# LickDetector.net
KiCad netlist of a schematic drawn in EAGLE
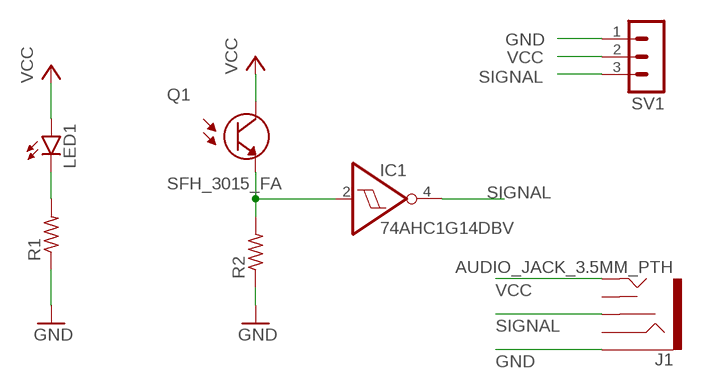
[diagram p0: schematic, sheet 1]

(export (version "E")
  (design (tool "Eeschema 10.0.6"))
  (components
    (comp (ref "IC1")
      (value "74AHC1G14DBV")
      (footprint "eagle-import:SOT23-5")
      (libsource (lib "eagle-import") (part "741G14DBVAHC"))
    )
    (comp (ref "J1")
      (value "AUDIO_JACK_3.5MM_PTH")
      (footprint "eagle-import:AUDIO-JACK")
      (libsource (lib "eagle-import") (part "AUDIO_JACK_3.5MM_PTH"))
    )
    (comp (ref "LED1")
      (value "LEDCHIPLED_1206")
      (footprint "eagle-import:CHIPLED_1206")
      (libsource (lib "eagle-import") (part "LEDCHIPLED_1206"))
    )
    (comp (ref "Q1")
      (value "SFH_3015_FA")
      (footprint "eagle-import:XDCR_SFH_3015_FA")
      (fields
        (field (name "DIGI-KEY_PART_NUMBER") "475-2914-1-ND")
        (field (name "MF") "OSRAM Opto")
        (field (name "MP") "SFH 3015 FA")
      )
      (libsource (lib "eagle-import") (part "SFH_3015_FA"))
    )
    (comp (ref "R1")
      (value "R-US_M1206")
      (footprint "eagle-import:M1206")
      (libsource (lib "eagle-import") (part "R-US_M1206"))
    )
    (comp (ref "R2")
      (value "R-US_M1206")
      (footprint "eagle-import:M1206")
      (libsource (lib "eagle-import") (part "R-US_M1206"))
    )
    (comp (ref "SV1")
      (value "MA03-1")
      (footprint "eagle-import:MA03-1")
      (libsource (lib "eagle-import") (part "MA03-1"))
    )
  )
  (nets
    (net (code "1") (name "/SIGNAL") (class "Default")
      (node (ref "IC1") (pin "4") (pinfunction "O_4") (pintype "output"))
      (node (ref "J1") (pin "RSH") (pinfunction "RSH_RSH") (pintype "bidirectional"))
      (node (ref "SV1") (pin "3") (pinfunction "3_3") (pintype "passive"))
    )
    (net (code "2") (name "GND") (class "Default")
      (node (ref "J1") (pin "SLEEVE") (pinfunction "SLEEVE_SLEEVE") (pintype "bidirectional"))
      (node (ref "R1") (pin "1") (pinfunction "1_1") (pintype "passive"))
      (node (ref "R2") (pin "1") (pinfunction "1_1") (pintype "passive"))
      (node (ref "SV1") (pin "1") (pinfunction "1_1") (pintype "passive"))
    )
    (net (code "3") (name "Net-(IC1A-I)") (class "Default")
      (node (ref "IC1") (pin "2") (pinfunction "I_2") (pintype "input"))
      (node (ref "Q1") (pin "1") (pinfunction "E_1") (pintype "passive"))
      (node (ref "R2") (pin "2") (pinfunction "2_2") (pintype "passive"))
    )
    (net (code "4") (name "Net-(LED1-PadC)") (class "Default")
      (node (ref "LED1") (pin "C") (pinfunction "C_C") (pintype "passive"))
      (node (ref "R1") (pin "2") (pinfunction "2_2") (pintype "passive"))
    )
    (net (code "5") (name "VCC") (class "Default")
      (node (ref "J1") (pin "TIP") (pinfunction "TIP_TIP") (pintype "bidirectional"))
      (node (ref "LED1") (pin "A") (pinfunction "A_A") (pintype "passive"))
      (node (ref "Q1") (pin "2") (pinfunction "C_2") (pintype "passive"))
      (node (ref "SV1") (pin "2") (pinfunction "2_2") (pintype "passive"))
    )
    (net (code "6") (name "unconnected-(J1-PadRING)") (class "Default")
      (node (ref "J1") (pin "RING") (pinfunction "RING_RING") (pintype "bidirectional"))
    )
    (net (code "7") (name "unconnected-(J1-PadTSH)") (class "Default")
      (node (ref "J1") (pin "TSH") (pinfunction "TSH_TSH") (pintype "bidirectional"))
    )
  )
)
